# on_off_switch_test.net
KiCad netlist of a schematic drawn in EAGLE
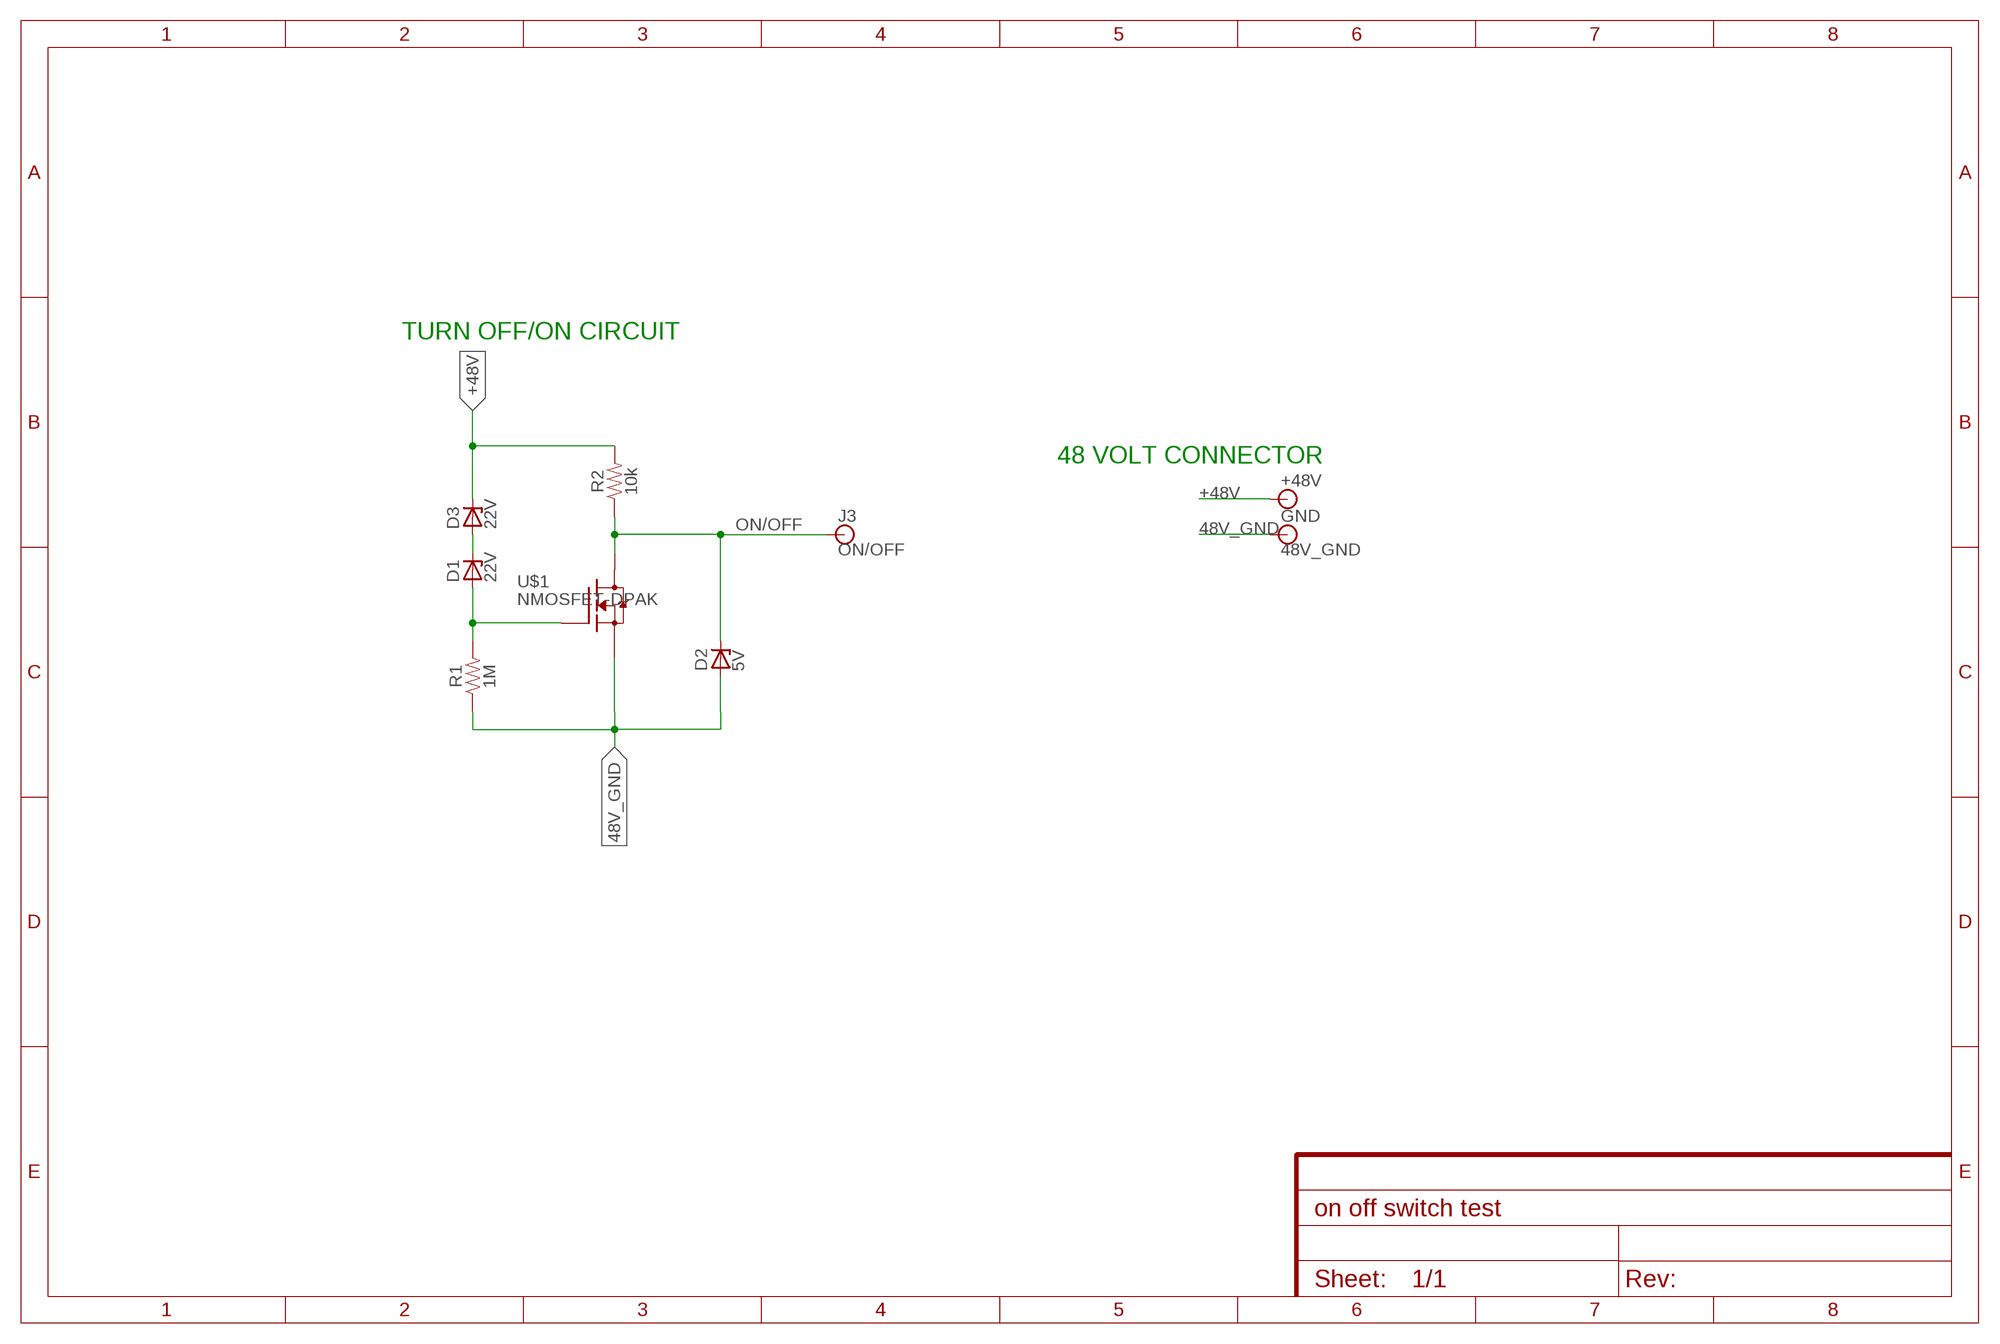
[diagram p0: schematic, sheet 1]

(export (version "E")
  (design (tool "Eeschema 10.0.6"))
  (components
    (comp (ref "+48V")
      (value "BANANA_CONN")
      (footprint "eagle-import:BANANA_CONN")
      (libsource (lib "eagle-import") (part "BANANA_CONN"))
    )
    (comp (ref "D1")
      (value "22V")
      (footprint "eagle-import:SOT23")
      (libsource (lib "eagle-import") (part "ZENER-DIODESOT23"))
    )
    (comp (ref "D2")
      (value "5V")
      (footprint "eagle-import:SOT23")
      (libsource (lib "eagle-import") (part "ZENER-DIODESOT23"))
    )
    (comp (ref "D3")
      (value "22V")
      (footprint "eagle-import:SOT23")
      (libsource (lib "eagle-import") (part "ZENER-DIODESOT23"))
    )
    (comp (ref "GND")
      (value "48V_GND")
      (footprint "eagle-import:BANANA_CONN")
      (libsource (lib "eagle-import") (part "BANANA_CONN"))
    )
    (comp (ref "J3")
      (value "ON/OFF")
      (footprint "eagle-import:BANANA_CONN")
      (libsource (lib "eagle-import") (part "SparkFun-Connectors_513_BANANA_CONN"))
    )
    (comp (ref "R1")
      (value "1M")
      (footprint "eagle-import:0603")
      (fields (field (name "SPICEPREFIX") "R"))
      (libsource (lib "eagle-import") (part "RESISTOR0603"))
    )
    (comp (ref "R2")
      (value "10k")
      (footprint "eagle-import:0603")
      (fields (field (name "SPICEPREFIX") "R"))
      (libsource (lib "eagle-import") (part "RESISTOR0603"))
    )
    (comp (ref "U$1")
      (value "NMOSFET-DPAK")
      (footprint "eagle-import:DPAK")
      (libsource (lib "eagle-import") (part "NMOSFET-DPAK"))
    )
  )
  (nets
    (net (code "1") (name "+48V") (class "Default")
      (node (ref "+48V") (pin "P$1") (pinfunction "1_P$1") (pintype "passive"))
      (node (ref "D3") (pin "3") (pinfunction "C_3") (pintype "passive"))
      (node (ref "R2") (pin "2") (pinfunction "2_2") (pintype "passive"))
    )
    (net (code "2") (name "/ON{slash}OFF") (class "Default")
      (node (ref "D2") (pin "3") (pinfunction "C_3") (pintype "passive"))
      (node (ref "J3") (pin "P$1") (pinfunction "1_P$1") (pintype "passive"))
      (node (ref "R2") (pin "1") (pinfunction "1_1") (pintype "passive"))
      (node (ref "U$1") (pin "4") (pinfunction "D1_4") (pintype "passive"))
    )
    (net (code "3") (name "48V_GND") (class "Default")
      (node (ref "D2") (pin "1") (pinfunction "A_1") (pintype "passive"))
      (node (ref "GND") (pin "P$1") (pinfunction "1_P$1") (pintype "passive"))
      (node (ref "R1") (pin "1") (pinfunction "1_1") (pintype "passive"))
      (node (ref "U$1") (pin "3") (pinfunction "S_3") (pintype "passive"))
    )
    (net (code "4") (name "Net-(D1-A)") (class "Default")
      (node (ref "D1") (pin "1") (pinfunction "A_1") (pintype "passive"))
      (node (ref "R1") (pin "2") (pinfunction "2_2") (pintype "passive"))
      (node (ref "U$1") (pin "1") (pinfunction "G_1") (pintype "passive"))
    )
    (net (code "5") (name "Net-(D1-C)") (class "Default")
      (node (ref "D1") (pin "3") (pinfunction "C_3") (pintype "passive"))
      (node (ref "D3") (pin "1") (pinfunction "A_1") (pintype "passive"))
    )
  )
)
